# bpod_stepper_1_4.net
KiCad netlist of a schematic drawn in EAGLE
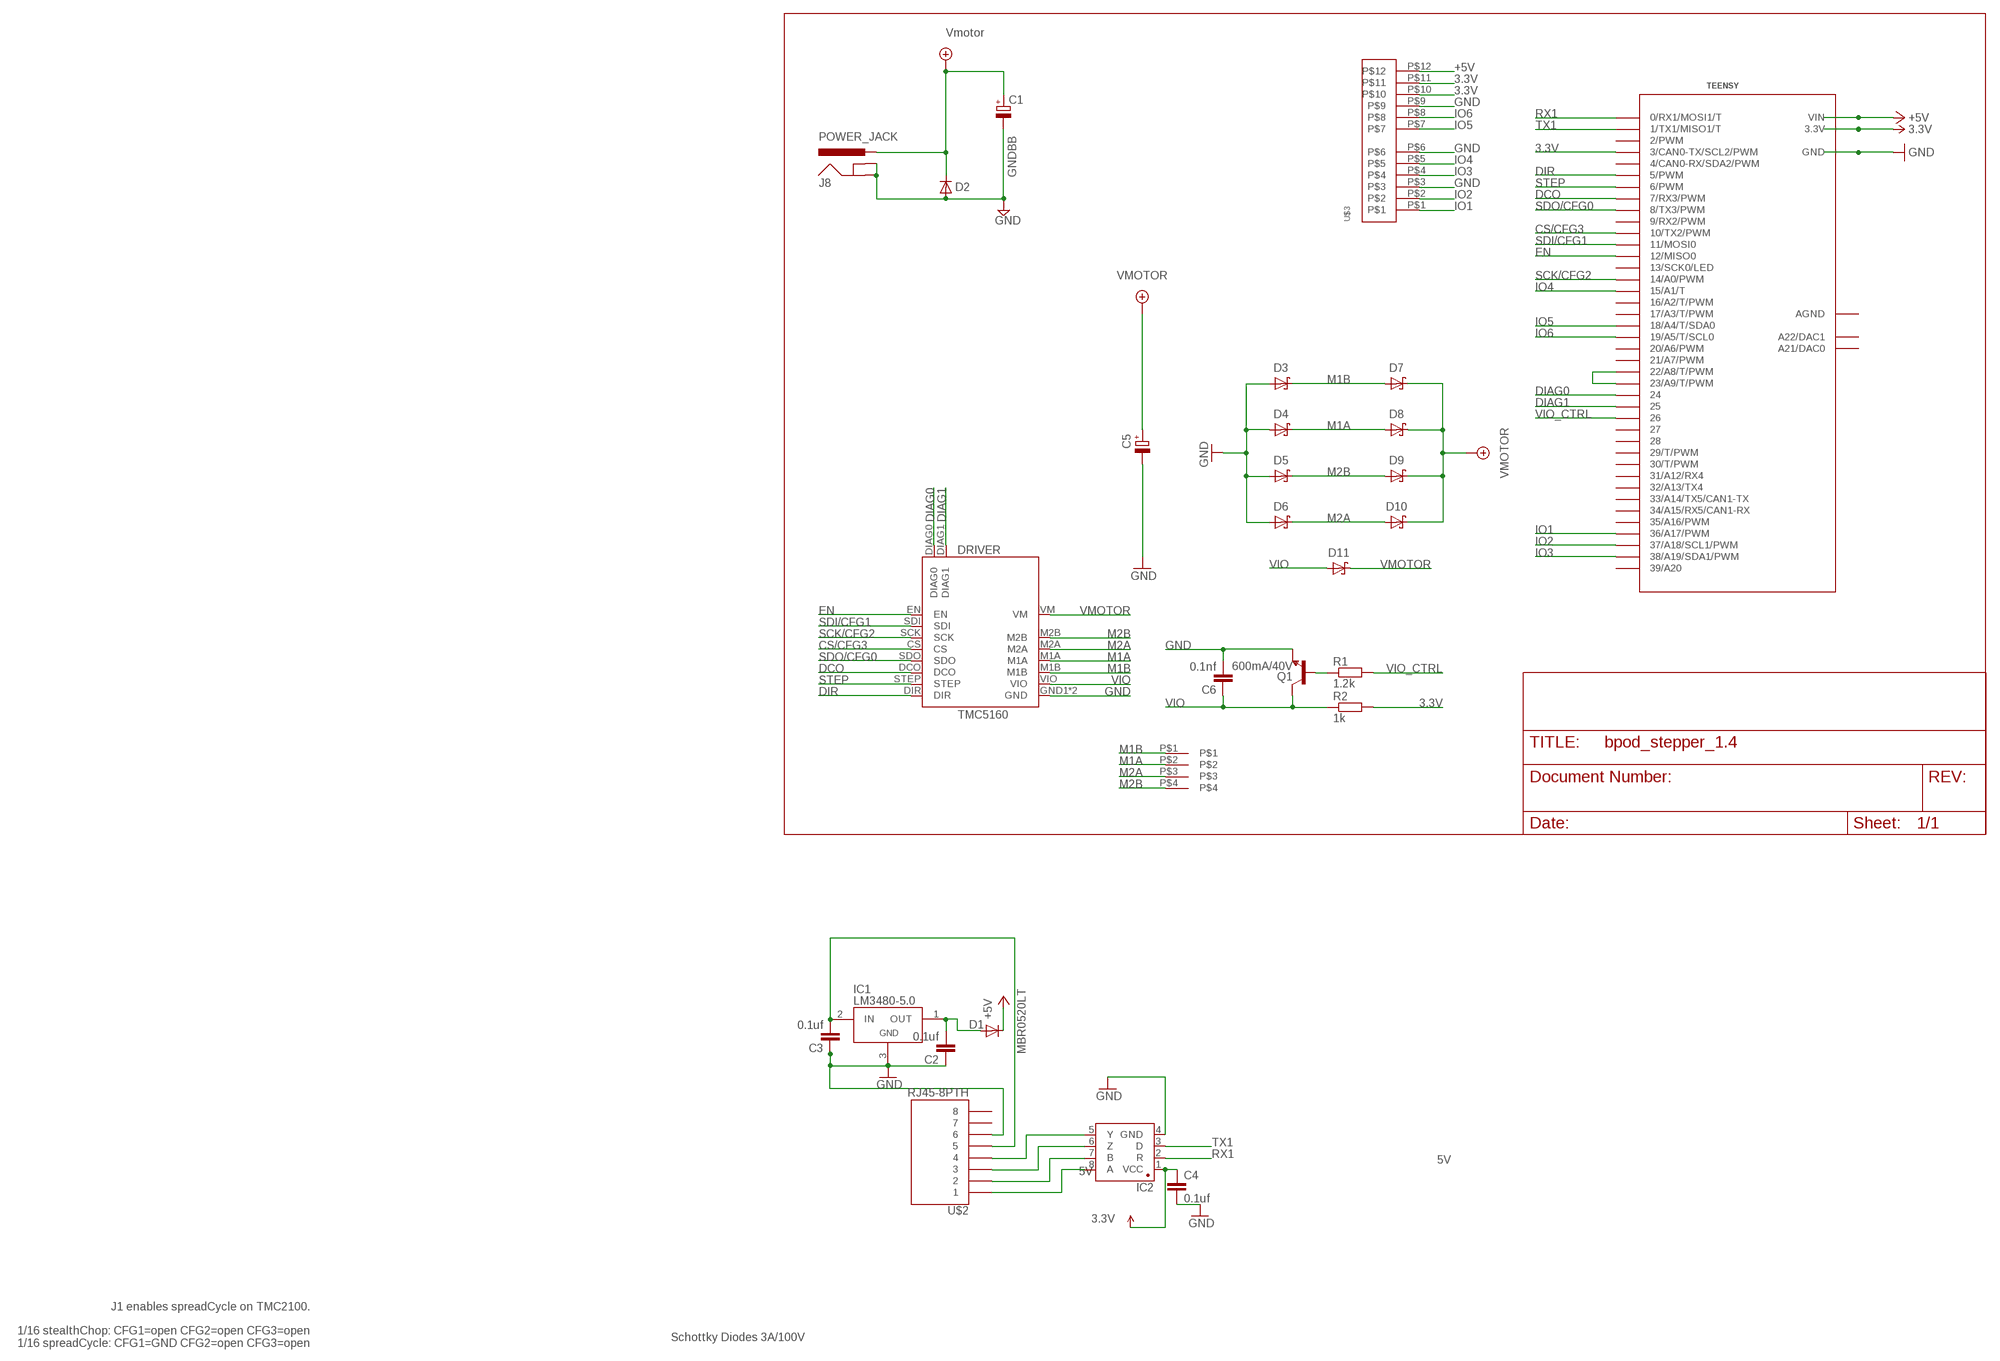
[diagram p0: schematic, sheet 1]

(export (version "E")
  (design (tool "Eeschema 10.0.6"))
  (components
    (comp (ref "C1")
      (value "CPOL-EUG")
      (footprint "eagle-import:PANASONIC_G")
      (libsource (lib "eagle-import") (part "CPOL-EUG"))
    )
    (comp (ref "C2")
      (value "0.1uf")
      (footprint "eagle-import:1206@1")
      (libsource (lib "eagle-import") (part "CAP1206"))
    )
    (comp (ref "C3")
      (value "0.1uf")
      (footprint "eagle-import:1206@1")
      (libsource (lib "eagle-import") (part "CAP1206"))
    )
    (comp (ref "C4")
      (value "0.1uf")
      (footprint "eagle-import:1206@1")
      (libsource (lib "eagle-import") (part "CAP1206"))
    )
    (comp (ref "C5")
      (value "CPOL-EUG")
      (footprint "eagle-import:PANASONIC_G")
      (libsource (lib "eagle-import") (part "CPOL-EUG"))
    )
    (comp (ref "C6")
      (value "0.1nf")
      (footprint "eagle-import:1206@1")
      (libsource (lib "eagle-import") (part "CAP1206"))
    )
    (comp (ref "D1")
      (value "MBR0520LT")
      (footprint "eagle-import:SOD123")
      (libsource (lib "eagle-import") (part "MBR0520LT"))
    )
    (comp (ref "D2")
      (value "DIODE-DO214AA")
      (footprint "eagle-import:DO214AA")
      (libsource (lib "eagle-import") (part "DIODE-DO214AA"))
    )
    (comp (ref "D3")
      (value "S310FA")
      (footprint "eagle-import:SOD123")
      (libsource (lib "eagle-import") (part "D_SCHOTTKY-SOD123"))
    )
    (comp (ref "D4")
      (value "S310FA")
      (footprint "eagle-import:SOD123")
      (libsource (lib "eagle-import") (part "D_SCHOTTKY-SOD123"))
    )
    (comp (ref "D5")
      (value "S310FA")
      (footprint "eagle-import:SOD123")
      (libsource (lib "eagle-import") (part "D_SCHOTTKY-SOD123"))
    )
    (comp (ref "D6")
      (value "S310FA")
      (footprint "eagle-import:SOD123")
      (libsource (lib "eagle-import") (part "D_SCHOTTKY-SOD123"))
    )
    (comp (ref "D7")
      (value "S310FA")
      (footprint "eagle-import:SOD123")
      (libsource (lib "eagle-import") (part "D_SCHOTTKY-SOD123"))
    )
    (comp (ref "D8")
      (value "S310FA")
      (footprint "eagle-import:SOD123")
      (libsource (lib "eagle-import") (part "D_SCHOTTKY-SOD123"))
    )
    (comp (ref "D9")
      (value "S310FA")
      (footprint "eagle-import:SOD123")
      (libsource (lib "eagle-import") (part "D_SCHOTTKY-SOD123"))
    )
    (comp (ref "D10")
      (value "S310FA")
      (footprint "eagle-import:SOD123")
      (libsource (lib "eagle-import") (part "D_SCHOTTKY-SOD123"))
    )
    (comp (ref "D11")
      (value "S310FA")
      (footprint "eagle-import:SOD123")
      (libsource (lib "eagle-import") (part "D_SCHOTTKY-SOD123"))
    )
    (comp (ref "DRIVER")
      (value "TMC5160")
      (footprint "eagle-import:TMC5160")
      (libsource (lib "eagle-import") (part "TMC5160"))
    )
    (comp (ref "IC1")
      (value "LM3480-5.0")
      (footprint "eagle-import:SOT-23-3")
      (libsource (lib "eagle-import") (part "LM3480-5.0"))
    )
    (comp (ref "IC2")
      (value "SN65HVD31DR")
      (footprint "eagle-import:SO08")
      (libsource (lib "eagle-import") (part "SN65HVD31DR"))
    )
    (comp (ref "J8")
      (value "POWER_JACK")
      (footprint "eagle-import:POWER_JACK_PTH")
      (libsource (lib "eagle-import") (part "POWER_JACK"))
    )
    (comp (ref "Q1")
      (value "600mA/40V")
      (footprint "eagle-import:SOT23-3")
      (libsource (lib "eagle-import") (part "TRANS_NPN-MMBT2222AL"))
    )
    (comp (ref "R1")
      (value "1.2k")
      (footprint "eagle-import:R1206")
      (libsource (lib "eagle-import") (part "R-EU_R1206"))
    )
    (comp (ref "R2")
      (value "1k")
      (footprint "eagle-import:R1206")
      (libsource (lib "eagle-import") (part "R-EU_R1206"))
    )
    (comp (ref "TEENSY")
      (value "TEENSY_3.6_DIL")
      (footprint "eagle-import:TEENSY_3.6_DIL")
      (libsource (lib "eagle-import") (part "TEENSY_3.6_DIL"))
    )
    (comp (ref "U$2")
      (value "RJ45-8PTH")
      (footprint "eagle-import:RJ45-8")
      (libsource (lib "eagle-import") (part "RJ45-8PTH"))
    )
    (comp (ref "U$3")
      (value "12POS_MOLEX_SOCKET")
      (footprint "eagle-import:12POS_MOLEX_SOCKET")
      (libsource (lib "eagle-import") (part "12POS_MOLEX_SOCKET"))
    )
    (comp (ref "U$4")
      (value "MOLEX395221004")
      (footprint "eagle-import:MOLEX395221004")
      (libsource (lib "eagle-import") (part "MOLEX395221004"))
    )
  )
  (nets
    (net (code "1") (name "+5V") (class "Default")
      (node (ref "D1") (pin "C") (pinfunction "C_C") (pintype "passive"))
      (node (ref "TEENSY") (pin "VIN") (pinfunction "VIN_VIN") (pintype "power_in"))
      (node (ref "U$3") (pin "P$12") (pinfunction "P$12_P$12") (pintype "bidirectional"))
    )
    (net (code "2") (name "/AGND") (class "Default")
      (node (ref "TEENSY") (pin "AGND") (pinfunction "AGND_AGND") (pintype "power_in"))
    )
    (net (code "3") (name "/CS{slash}CFG3") (class "Default")
      (node (ref "DRIVER") (pin "CS") (pinfunction "CS_CS") (pintype "passive"))
      (node (ref "TEENSY") (pin "10") (pinfunction "10/TX2/PWM_10") (pintype "bidirectional"))
    )
    (net (code "4") (name "/DCO") (class "Default")
      (node (ref "DRIVER") (pin "DCO") (pinfunction "DCO_DCO") (pintype "passive"))
      (node (ref "TEENSY") (pin "7") (pinfunction "7/RX3/PWM_7") (pintype "bidirectional"))
    )
    (net (code "5") (name "/DIAG0") (class "Default")
      (node (ref "DRIVER") (pin "DIAG0") (pinfunction "DIAG0_DIAG0") (pintype "passive"))
      (node (ref "TEENSY") (pin "24") (pinfunction "24_24") (pintype "bidirectional"))
    )
    (net (code "6") (name "/DIAG1") (class "Default")
      (node (ref "DRIVER") (pin "DIAG1") (pinfunction "DIAG1_DIAG1") (pintype "passive"))
      (node (ref "TEENSY") (pin "25") (pinfunction "25_25") (pintype "bidirectional"))
    )
    (net (code "7") (name "/DIR") (class "Default")
      (node (ref "DRIVER") (pin "DIR") (pinfunction "DIR_DIR") (pintype "input"))
      (node (ref "TEENSY") (pin "5") (pinfunction "5/PWM_5") (pintype "bidirectional"))
    )
    (net (code "8") (name "/EN") (class "Default")
      (node (ref "DRIVER") (pin "EN") (pinfunction "EN_EN") (pintype "passive"))
      (node (ref "TEENSY") (pin "12") (pinfunction "12/MISO0_12") (pintype "bidirectional"))
    )
    (net (code "9") (name "/IO1") (class "Default")
      (node (ref "TEENSY") (pin "36/A17") (pinfunction "36/A17/PWM_36/A17") (pintype "bidirectional"))
      (node (ref "U$3") (pin "P$1") (pinfunction "P$1_P$1") (pintype "bidirectional"))
    )
    (net (code "10") (name "/IO2") (class "Default")
      (node (ref "TEENSY") (pin "37/A18") (pinfunction "37/A18/SCL1/PWM_37/A18") (pintype "bidirectional"))
      (node (ref "U$3") (pin "P$2") (pinfunction "P$2_P$2") (pintype "bidirectional"))
    )
    (net (code "11") (name "/IO3") (class "Default")
      (node (ref "TEENSY") (pin "38/A19") (pinfunction "38/A19/SDA1/PWM_38/A19") (pintype "bidirectional"))
      (node (ref "U$3") (pin "P$4") (pinfunction "P$4_P$4") (pintype "bidirectional"))
    )
    (net (code "12") (name "/IO4") (class "Default")
      (node (ref "TEENSY") (pin "15/A1") (pinfunction "15/A1/T_15/A1") (pintype "bidirectional"))
      (node (ref "U$3") (pin "P$5") (pinfunction "P$5_P$5") (pintype "bidirectional"))
    )
    (net (code "13") (name "/IO5") (class "Default")
      (node (ref "TEENSY") (pin "18/A4") (pinfunction "18/A4/T/SDA0_18/A4") (pintype "bidirectional"))
      (node (ref "U$3") (pin "P$7") (pinfunction "P$7_P$7") (pintype "bidirectional"))
    )
    (net (code "14") (name "/IO6") (class "Default")
      (node (ref "TEENSY") (pin "19/A5") (pinfunction "19/A5/T/SCL0_19/A5") (pintype "bidirectional"))
      (node (ref "U$3") (pin "P$8") (pinfunction "P$8_P$8") (pintype "bidirectional"))
    )
    (net (code "15") (name "/M1A") (class "Default")
      (node (ref "D4") (pin "C") (pinfunction "C_C") (pintype "passive"))
      (node (ref "D8") (pin "A") (pinfunction "A_A") (pintype "passive"))
      (node (ref "DRIVER") (pin "M1A") (pinfunction "M1A_M1A") (pintype "output"))
      (node (ref "U$4") (pin "P$2") (pinfunction "P$2_P$2") (pintype "bidirectional"))
    )
    (net (code "16") (name "/M1B") (class "Default")
      (node (ref "D3") (pin "C") (pinfunction "C_C") (pintype "passive"))
      (node (ref "D7") (pin "A") (pinfunction "A_A") (pintype "passive"))
      (node (ref "DRIVER") (pin "M1B") (pinfunction "M1B_M1B") (pintype "output"))
      (node (ref "U$4") (pin "P$1") (pinfunction "P$1_P$1") (pintype "bidirectional"))
    )
    (net (code "17") (name "/M2A") (class "Default")
      (node (ref "D10") (pin "A") (pinfunction "A_A") (pintype "passive"))
      (node (ref "D6") (pin "C") (pinfunction "C_C") (pintype "passive"))
      (node (ref "DRIVER") (pin "M2A") (pinfunction "M2A_M2A") (pintype "output"))
      (node (ref "U$4") (pin "P$3") (pinfunction "P$3_P$3") (pintype "bidirectional"))
    )
    (net (code "18") (name "/M2B") (class "Default")
      (node (ref "D5") (pin "C") (pinfunction "C_C") (pintype "passive"))
      (node (ref "D9") (pin "A") (pinfunction "A_A") (pintype "passive"))
      (node (ref "DRIVER") (pin "M2B") (pinfunction "M2B_M2B") (pintype "output"))
      (node (ref "U$4") (pin "P$4") (pinfunction "P$4_P$4") (pintype "bidirectional"))
    )
    (net (code "19") (name "/RX1") (class "Default")
      (node (ref "IC2") (pin "2") (pinfunction "R_2") (pintype "bidirectional"))
      (node (ref "TEENSY") (pin "0") (pinfunction "0/RX1/MOSI1/T_0") (pintype "bidirectional"))
    )
    (net (code "20") (name "/SCK{slash}CFG2") (class "Default")
      (node (ref "DRIVER") (pin "SCK") (pinfunction "SCK_SCK") (pintype "passive"))
      (node (ref "TEENSY") (pin "14/A0") (pinfunction "14/A0/PWM_14/A0") (pintype "bidirectional"))
    )
    (net (code "21") (name "/SDI{slash}CFG1") (class "Default")
      (node (ref "DRIVER") (pin "SDI") (pinfunction "SDI_SDI") (pintype "passive"))
      (node (ref "TEENSY") (pin "11") (pinfunction "11/MOSI0_11") (pintype "bidirectional"))
    )
    (net (code "22") (name "/SDO{slash}CFG0") (class "Default")
      (node (ref "DRIVER") (pin "SDO") (pinfunction "SDO_SDO") (pintype "passive"))
      (node (ref "TEENSY") (pin "8") (pinfunction "8/TX3/PWM_8") (pintype "bidirectional"))
    )
    (net (code "23") (name "/STEP") (class "Default")
      (node (ref "DRIVER") (pin "STEP") (pinfunction "STEP_STEP") (pintype "input"))
      (node (ref "TEENSY") (pin "6") (pinfunction "6/PWM_6") (pintype "bidirectional"))
    )
    (net (code "24") (name "/TX1") (class "Default")
      (node (ref "IC2") (pin "3") (pinfunction "D_3") (pintype "bidirectional"))
      (node (ref "TEENSY") (pin "1") (pinfunction "1/TX1/MISO1/T_1") (pintype "bidirectional"))
    )
    (net (code "25") (name "/VIO") (class "Default")
      (node (ref "C6") (pin "1") (pinfunction "1_1") (pintype "passive"))
      (node (ref "D11") (pin "A") (pinfunction "A_A") (pintype "passive"))
      (node (ref "DRIVER") (pin "VIO") (pinfunction "VIO_VIO") (pintype "power_in"))
      (node (ref "Q1") (pin "3") (pinfunction "C_3") (pintype "passive"))
      (node (ref "R2") (pin "1") (pinfunction "1_1") (pintype "passive"))
    )
    (net (code "26") (name "/VIO_CTRL") (class "Default")
      (node (ref "R1") (pin "2") (pinfunction "2_2") (pintype "passive"))
      (node (ref "TEENSY") (pin "26") (pinfunction "26_26") (pintype "bidirectional"))
    )
    (net (code "27") (name "3.3V") (class "Default")
      (node (ref "C4") (pin "1") (pinfunction "1_1") (pintype "passive"))
      (node (ref "IC2") (pin "1") (pinfunction "VCC_1") (pintype "bidirectional"))
      (node (ref "R2") (pin "2") (pinfunction "2_2") (pintype "passive"))
      (node (ref "TEENSY") (pin "3") (pinfunction "3/CAN0-TX/SCL2/PWM_3") (pintype "bidirectional"))
      (node (ref "TEENSY") (pin "3.3V") (pinfunction "3.3V_3.3V") (pintype "power_in"))
      (node (ref "TEENSY") (pin "3.3V3") (pinfunction "3.3V_3.3V3") (pintype "power_in"))
      (node (ref "U$3") (pin "P$10") (pinfunction "P$10_P$10") (pintype "bidirectional"))
      (node (ref "U$3") (pin "P$11") (pinfunction "P$11_P$11") (pintype "bidirectional"))
    )
    (net (code "28") (name "GND") (class "Default")
      (node (ref "C1") (pin "-") (pinfunction "-_-") (pintype "passive"))
      (node (ref "C2") (pin "1") (pinfunction "1_1") (pintype "passive"))
      (node (ref "C3") (pin "1") (pinfunction "1_1") (pintype "passive"))
      (node (ref "C4") (pin "2") (pinfunction "2_2") (pintype "passive"))
      (node (ref "C5") (pin "-") (pinfunction "-_-") (pintype "passive"))
      (node (ref "C6") (pin "2") (pinfunction "2_2") (pintype "passive"))
      (node (ref "D2") (pin "A") (pinfunction "A_A") (pintype "passive"))
      (node (ref "D3") (pin "A") (pinfunction "A_A") (pintype "passive"))
      (node (ref "D4") (pin "A") (pinfunction "A_A") (pintype "passive"))
      (node (ref "D5") (pin "A") (pinfunction "A_A") (pintype "passive"))
      (node (ref "D6") (pin "A") (pinfunction "A_A") (pintype "passive"))
      (node (ref "DRIVER") (pin "GND1") (pinfunction "GND_GND1") (pintype "power_in"))
      (node (ref "DRIVER") (pin "GND2") (pinfunction "GND_GND2") (pintype "power_in"))
      (node (ref "IC1") (pin "3") (pinfunction "GND_3") (pintype "power_in"))
      (node (ref "IC2") (pin "4") (pinfunction "GND_4") (pintype "bidirectional"))
      (node (ref "J8") (pin "GND") (pinfunction "GND_GND") (pintype "bidirectional"))
      (node (ref "J8") (pin "GNDBREAK") (pinfunction "GNDBREAK_GNDBREAK") (pintype "bidirectional"))
      (node (ref "Q1") (pin "2") (pinfunction "E_2") (pintype "passive"))
      (node (ref "TEENSY") (pin "GND") (pinfunction "GND_GND") (pintype "power_in"))
      (node (ref "TEENSY") (pin "GND1") (pinfunction "GND_GND1") (pintype "power_in"))
      (node (ref "U$2") (pin "6") (pinfunction "6_6") (pintype "bidirectional"))
      (node (ref "U$3") (pin "P$3") (pinfunction "P$3_P$3") (pintype "bidirectional"))
      (node (ref "U$3") (pin "P$6") (pinfunction "P$6_P$6") (pintype "bidirectional"))
      (node (ref "U$3") (pin "P$9") (pinfunction "P$9_P$9") (pintype "bidirectional"))
    )
    (net (code "29") (name "Net-(IC1-IN)") (class "Default")
      (node (ref "C3") (pin "2") (pinfunction "2_2") (pintype "passive"))
      (node (ref "IC1") (pin "2") (pinfunction "IN_2") (pintype "power_in"))
      (node (ref "U$2") (pin "5") (pinfunction "5_5") (pintype "bidirectional"))
    )
    (net (code "30") (name "Net-(IC1-OUT)") (class "Default")
      (node (ref "C2") (pin "2") (pinfunction "2_2") (pintype "passive"))
      (node (ref "D1") (pin "A") (pinfunction "A_A") (pintype "passive"))
      (node (ref "IC1") (pin "1") (pinfunction "OUT_1") (pintype "power_in"))
    )
    (net (code "31") (name "Net-(IC2-A)") (class "Default")
      (node (ref "IC2") (pin "8") (pinfunction "A_8") (pintype "bidirectional"))
      (node (ref "U$2") (pin "1") (pinfunction "1_1") (pintype "bidirectional"))
    )
    (net (code "32") (name "Net-(IC2-B)") (class "Default")
      (node (ref "IC2") (pin "7") (pinfunction "B_7") (pintype "bidirectional"))
      (node (ref "U$2") (pin "2") (pinfunction "2_2") (pintype "bidirectional"))
    )
    (net (code "33") (name "Net-(IC2-Y)") (class "Default")
      (node (ref "IC2") (pin "5") (pinfunction "Y_5") (pintype "bidirectional"))
      (node (ref "U$2") (pin "4") (pinfunction "4_4") (pintype "bidirectional"))
    )
    (net (code "34") (name "Net-(IC2-Z)") (class "Default")
      (node (ref "IC2") (pin "6") (pinfunction "Z_6") (pintype "bidirectional"))
      (node (ref "U$2") (pin "3") (pinfunction "3_3") (pintype "bidirectional"))
    )
    (net (code "35") (name "Net-(Q1-B)") (class "Default")
      (node (ref "Q1") (pin "1") (pinfunction "B_1") (pintype "passive"))
      (node (ref "R1") (pin "1") (pinfunction "1_1") (pintype "passive"))
    )
    (net (code "36") (name "Net-(TEENSY-22{slash}A8{slash}T{slash}PWM)") (class "Default")
      (node (ref "TEENSY") (pin "22/A8") (pinfunction "22/A8/T/PWM_22/A8") (pintype "bidirectional"))
      (node (ref "TEENSY") (pin "23/A9") (pinfunction "23/A9/T/PWM_23/A9") (pintype "bidirectional"))
    )
    (net (code "37") (name "Vmotor") (class "Default")
      (node (ref "C1") (pin "+") (pinfunction "+_+") (pintype "passive"))
      (node (ref "C5") (pin "+") (pinfunction "+_+") (pintype "passive"))
      (node (ref "D10") (pin "C") (pinfunction "C_C") (pintype "passive"))
      (node (ref "D11") (pin "C") (pinfunction "C_C") (pintype "passive"))
      (node (ref "D2") (pin "C") (pinfunction "C_C") (pintype "passive"))
      (node (ref "D7") (pin "C") (pinfunction "C_C") (pintype "passive"))
      (node (ref "D8") (pin "C") (pinfunction "C_C") (pintype "passive"))
      (node (ref "D9") (pin "C") (pinfunction "C_C") (pintype "passive"))
      (node (ref "DRIVER") (pin "VM") (pinfunction "VM_VM") (pintype "power_in"))
      (node (ref "J8") (pin "PWR") (pinfunction "PWR_PWR") (pintype "bidirectional"))
    )
    (net (code "38") (name "unconnected-(TEENSY-2{slash}PWM-Pad2)") (class "Default")
      (node (ref "TEENSY") (pin "2") (pinfunction "2/PWM_2") (pintype "bidirectional"))
    )
    (net (code "39") (name "unconnected-(TEENSY-4{slash}CAN0-RX{slash}SDA2{slash}PWM-Pad4)") (class "Default")
      (node (ref "TEENSY") (pin "4") (pinfunction "4/CAN0-RX/SDA2/PWM_4") (pintype "bidirectional"))
    )
    (net (code "40") (name "unconnected-(TEENSY-9{slash}RX2{slash}PWM-Pad9)") (class "Default")
      (node (ref "TEENSY") (pin "9") (pinfunction "9/RX2/PWM_9") (pintype "bidirectional"))
    )
    (net (code "41") (name "unconnected-(TEENSY-13{slash}SCK0{slash}LED-Pad13)") (class "Default")
      (node (ref "TEENSY") (pin "13") (pinfunction "13/SCK0/LED_13") (pintype "bidirectional"))
    )
    (net (code "42") (name "unconnected-(TEENSY-16{slash}A2{slash}T{slash}PWM-Pad16{slash}A2)") (class "Default")
      (node (ref "TEENSY") (pin "16/A2") (pinfunction "16/A2/T/PWM_16/A2") (pintype "bidirectional"))
    )
    (net (code "43") (name "unconnected-(TEENSY-17{slash}A3{slash}T{slash}PWM-Pad17{slash}A3)") (class "Default")
      (node (ref "TEENSY") (pin "17/A3") (pinfunction "17/A3/T/PWM_17/A3") (pintype "bidirectional"))
    )
    (net (code "44") (name "unconnected-(TEENSY-20{slash}A6{slash}PWM-Pad20{slash}A6)") (class "Default")
      (node (ref "TEENSY") (pin "20/A6") (pinfunction "20/A6/PWM_20/A6") (pintype "bidirectional"))
    )
    (net (code "45") (name "unconnected-(TEENSY-21{slash}A7{slash}PWM-Pad21{slash}A7)") (class "Default")
      (node (ref "TEENSY") (pin "21/A7") (pinfunction "21/A7/PWM_21/A7") (pintype "bidirectional"))
    )
    (net (code "46") (name "unconnected-(TEENSY-29{slash}T{slash}PWM-Pad29)") (class "Default")
      (node (ref "TEENSY") (pin "29") (pinfunction "29/T/PWM_29") (pintype "bidirectional"))
    )
    (net (code "47") (name "unconnected-(TEENSY-30{slash}T{slash}PWM-Pad30)") (class "Default")
      (node (ref "TEENSY") (pin "30") (pinfunction "30/T/PWM_30") (pintype "bidirectional"))
    )
    (net (code "48") (name "unconnected-(TEENSY-31{slash}A12{slash}RX4-Pad31{slash}A12)") (class "Default")
      (node (ref "TEENSY") (pin "31/A12") (pinfunction "31/A12/RX4_31/A12") (pintype "bidirectional"))
    )
    (net (code "49") (name "unconnected-(TEENSY-32{slash}A13{slash}TX4-Pad32{slash}A13)") (class "Default")
      (node (ref "TEENSY") (pin "32/A13") (pinfunction "32/A13/TX4_32/A13") (pintype "bidirectional"))
    )
    (net (code "50") (name "unconnected-(TEENSY-33{slash}A14{slash}TX5{slash}CAN1-TX-Pad33{slash}A14)") (class "Default")
      (node (ref "TEENSY") (pin "33/A14") (pinfunction "33/A14/TX5/CAN1-TX_33/A14") (pintype "bidirectional"))
    )
    (net (code "51") (name "unconnected-(TEENSY-34{slash}A15{slash}RX5{slash}CAN1-RX-Pad34{slash}A15)") (class "Default")
      (node (ref "TEENSY") (pin "34/A15") (pinfunction "34/A15/RX5/CAN1-RX_34/A15") (pintype "bidirectional"))
    )
    (net (code "52") (name "unconnected-(TEENSY-35{slash}A16{slash}PWM-Pad35{slash}A16)") (class "Default")
      (node (ref "TEENSY") (pin "35/A16") (pinfunction "35/A16/PWM_35/A16") (pintype "bidirectional"))
    )
    (net (code "53") (name "unconnected-(TEENSY-A21{slash}DAC0-PadA21)") (class "Default")
      (node (ref "TEENSY") (pin "A21") (pinfunction "A21/DAC0_A21") (pintype "bidirectional"))
    )
    (net (code "54") (name "unconnected-(TEENSY-A22{slash}DAC1-PadA22)") (class "Default")
      (node (ref "TEENSY") (pin "A22") (pinfunction "A22/DAC1_A22") (pintype "bidirectional"))
    )
    (net (code "55") (name "unconnected-(TEENSY-Pad27)") (class "Default")
      (node (ref "TEENSY") (pin "27") (pinfunction "27_27") (pintype "bidirectional"))
    )
    (net (code "56") (name "unconnected-(TEENSY-Pad28)") (class "Default")
      (node (ref "TEENSY") (pin "28") (pinfunction "28_28") (pintype "bidirectional"))
    )
    (net (code "57") (name "unconnected-(TEENSY-Pad39{slash}A20)") (class "Default")
      (node (ref "TEENSY") (pin "39/A20") (pinfunction "39/A20_39/A20") (pintype "bidirectional"))
    )
    (net (code "58") (name "unconnected-(U$2-Pad7)") (class "Default")
      (node (ref "U$2") (pin "7") (pinfunction "7_7") (pintype "bidirectional"))
    )
    (net (code "59") (name "unconnected-(U$2-Pad8)") (class "Default")
      (node (ref "U$2") (pin "8") (pinfunction "8_8") (pintype "bidirectional"))
    )
  )
)
